# Float_Main_PCB.net
KiCad netlist of a schematic drawn in Altium Designer
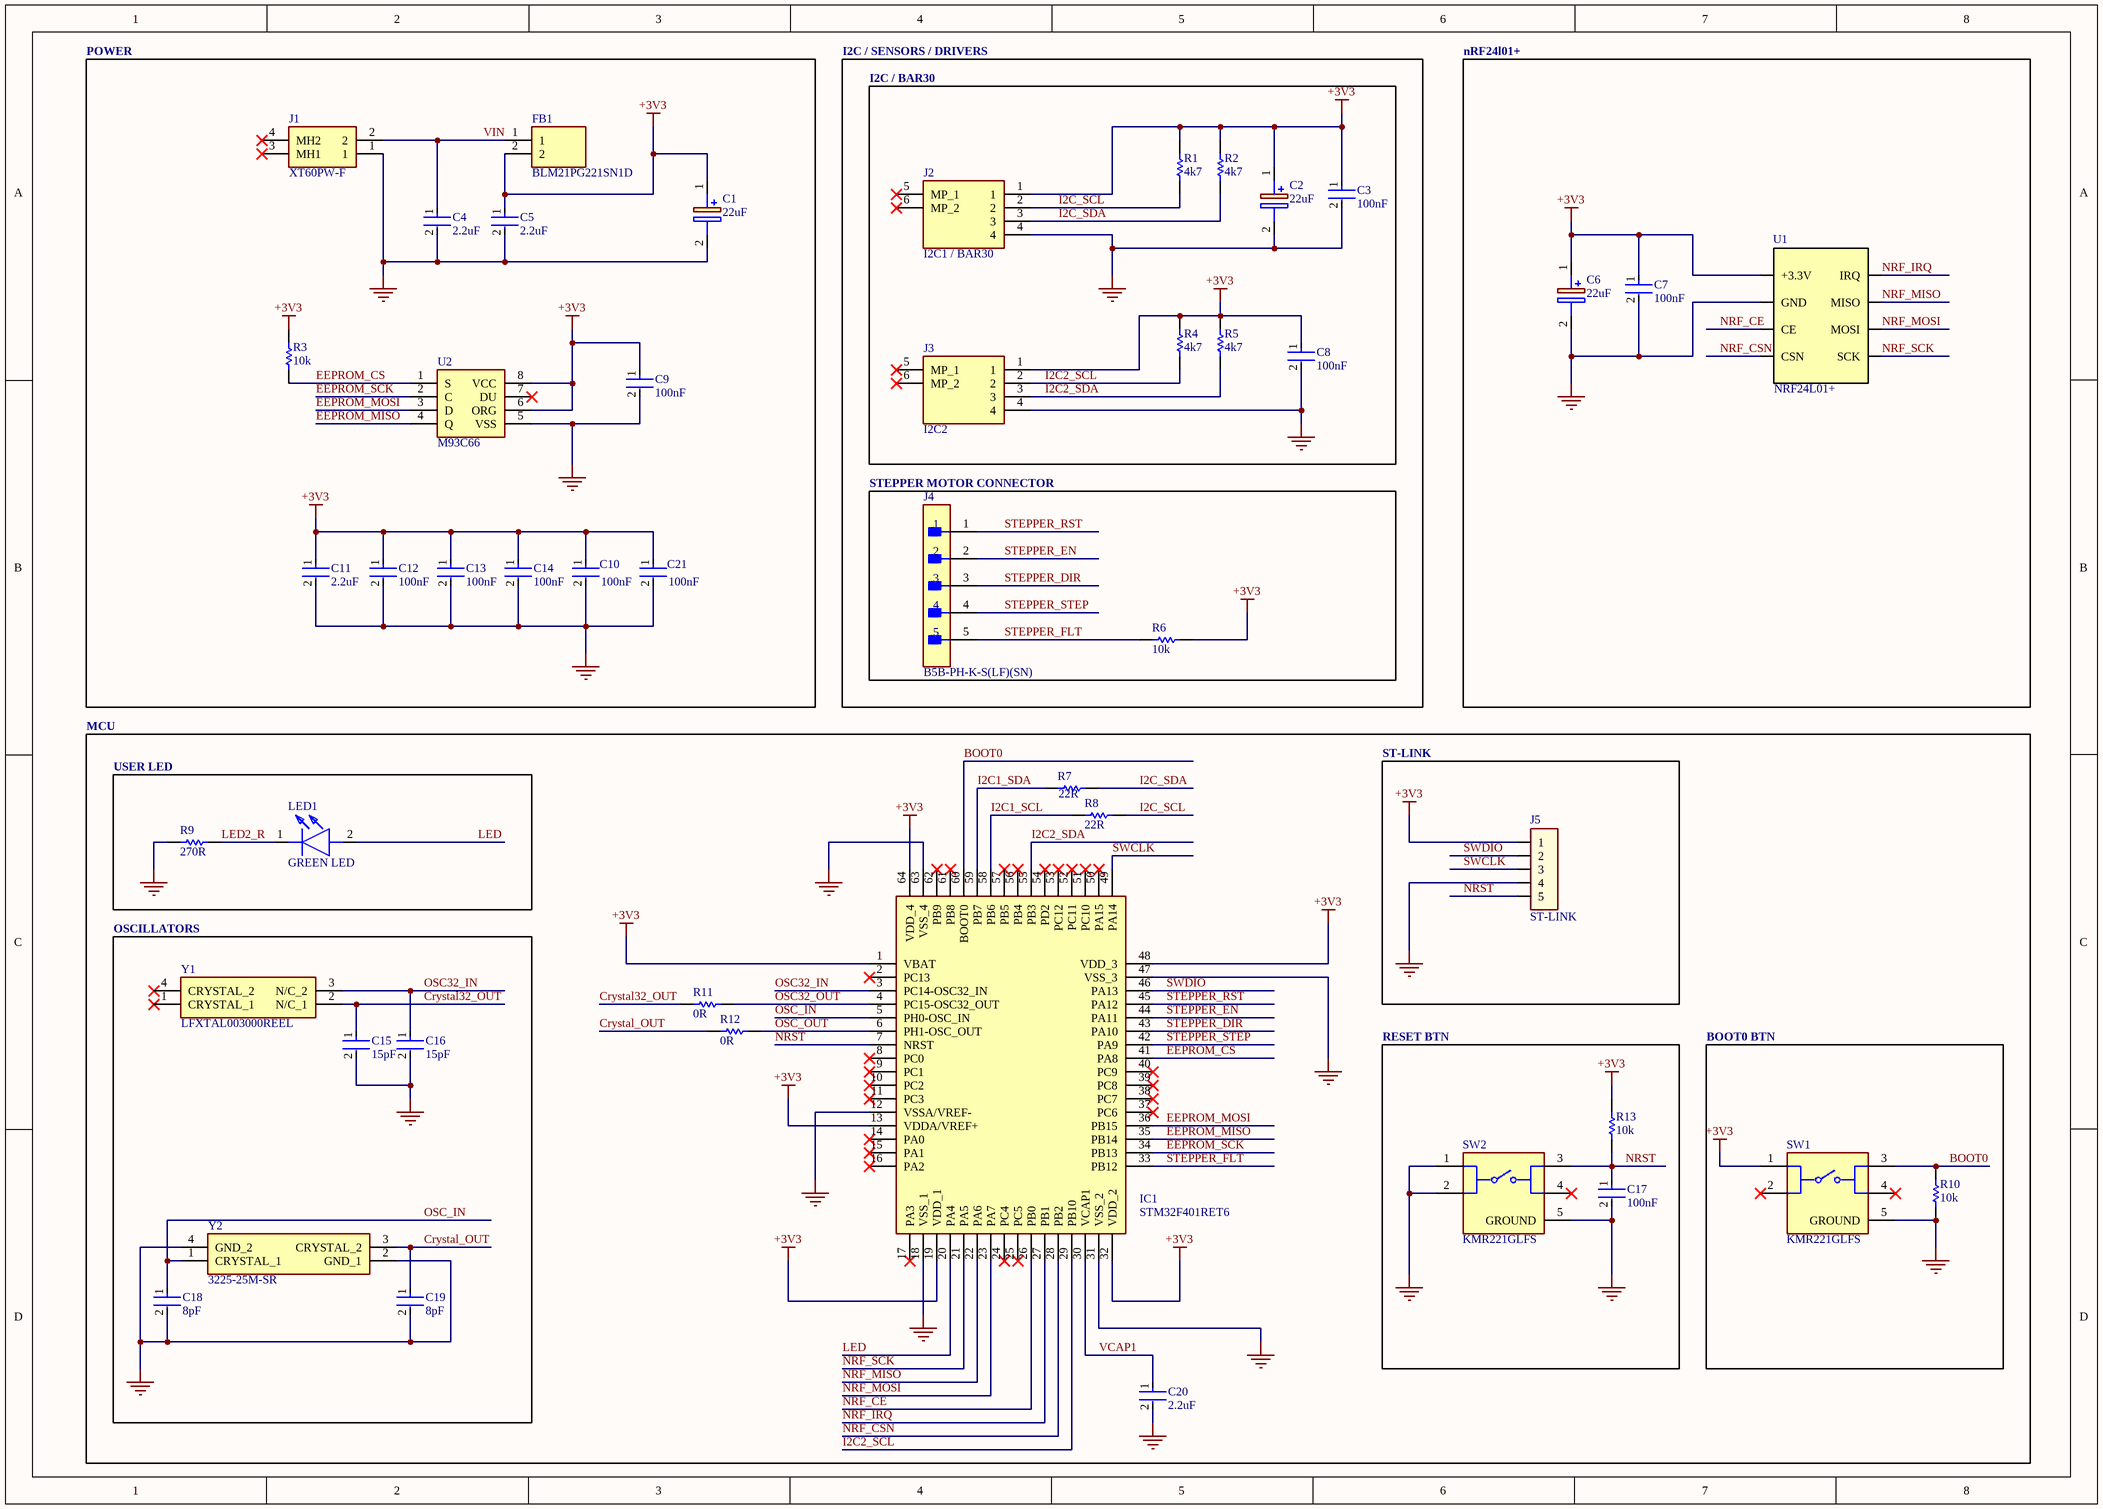
[diagram p0: Float_Main_PCB.SchDoc]

(export (version "E")
  (design (tool "Eeschema 10.0.6"))
  (components
    (comp (ref "C1")
      (value "22uF")
      (footprint "SamacSys:EEE1AA220WR")
      (description "Capacitor Polarised")
      (fields (field (name "MANUFACTURER_PART_NUMBER") "EEE1CA100SR"))
      (libsource (lib "*") (part "EEE1CA100SR"))
    )
    (comp (ref "C2")
      (value "22uF")
      (footprint "SamacSys:EEE1AA220WR")
      (description "Capacitor Polarised")
      (fields (field (name "MANUFACTURER_PART_NUMBER") "EEE1CA100SR"))
      (libsource (lib "*") (part "EEE1CA100SR"))
    )
    (comp (ref "C3")
      (value "100nF")
      (footprint "FP-0805-L_2_01_0_2-W_1_25-MFG")
      (fields (field (name "TOLERANCE") "10%") (field (name "VOLTAGE") "10V"))
      (libsource (lib "Altium Content Vault") (part "b4654b650e69147ec39a6b967a45e02"))
    )
    (comp (ref "C4")
      (value "2.2uF")
      (footprint "FP-0805-L_2_01_0_2-W_1_25-MFG")
      (fields (field (name "TOLERANCE") "10%") (field (name "VOLTAGE") "10V"))
      (libsource (lib "Altium Content Vault") (part "b4654b650e69147ec39a6b967a45e02"))
    )
    (comp (ref "C5")
      (value "2.2uF")
      (footprint "FP-0805-L_2_01_0_2-W_1_25-MFG")
      (fields (field (name "TOLERANCE") "10%") (field (name "VOLTAGE") "10V"))
      (libsource (lib "Altium Content Vault") (part "b4654b650e69147ec39a6b967a45e02"))
    )
    (comp (ref "C6")
      (value "22uF")
      (footprint "SamacSys:EEE1AA220WR")
      (description "Capacitor Polarised")
      (fields (field (name "MANUFACTURER_PART_NUMBER") "EEE1CA100SR"))
      (libsource (lib "*") (part "EEE1CA100SR"))
    )
    (comp (ref "C7")
      (value "100nF")
      (footprint "FP-0805-L_2_01_0_2-W_1_25-MFG")
      (fields (field (name "TOLERANCE") "10%") (field (name "VOLTAGE") "10V"))
      (libsource (lib "Altium Content Vault") (part "b4654b650e69147ec39a6b967a45e02"))
    )
    (comp (ref "C8")
      (value "100nF")
      (footprint "FP-0805-L_2_01_0_2-W_1_25-MFG")
      (fields (field (name "TOLERANCE") "10%") (field (name "VOLTAGE") "10V"))
      (libsource (lib "Altium Content Vault") (part "b4654b650e69147ec39a6b967a45e02"))
    )
    (comp (ref "C9")
      (value "100nF")
      (footprint "FP-0805-L_2_01_0_2-W_1_25-MFG")
      (fields (field (name "TOLERANCE") "10%") (field (name "VOLTAGE") "10V"))
      (libsource (lib "Altium Content Vault") (part "b4654b650e69147ec39a6b967a45e02"))
    )
    (comp (ref "C10")
      (value "100nF")
      (footprint "FP-0805-L_2_01_0_2-W_1_25-MFG")
      (fields (field (name "TOLERANCE") "10%") (field (name "VOLTAGE") "10V"))
      (libsource (lib "Altium Content Vault") (part "b4654b650e69147ec39a6b967a45e02"))
    )
    (comp (ref "C11")
      (value "2.2uF")
      (footprint "FP-0805-L_2_01_0_2-W_1_25-MFG")
      (fields (field (name "TOLERANCE") "10%") (field (name "VOLTAGE") "10V"))
      (libsource (lib "Altium Content Vault") (part "b4654b650e69147ec39a6b967a45e02"))
    )
    (comp (ref "C12")
      (value "100nF")
      (footprint "FP-0805-L_2_01_0_2-W_1_25-MFG")
      (fields (field (name "TOLERANCE") "10%") (field (name "VOLTAGE") "10V"))
      (libsource (lib "Altium Content Vault") (part "b4654b650e69147ec39a6b967a45e02"))
    )
    (comp (ref "C13")
      (value "100nF")
      (footprint "FP-0805-L_2_01_0_2-W_1_25-MFG")
      (fields (field (name "TOLERANCE") "10%") (field (name "VOLTAGE") "10V"))
      (libsource (lib "Altium Content Vault") (part "b4654b650e69147ec39a6b967a45e02"))
    )
    (comp (ref "C14")
      (value "100nF")
      (footprint "FP-0805-L_2_01_0_2-W_1_25-MFG")
      (fields (field (name "TOLERANCE") "10%") (field (name "VOLTAGE") "10V"))
      (libsource (lib "Altium Content Vault") (part "b4654b650e69147ec39a6b967a45e02"))
    )
    (comp (ref "C15")
      (value "15pF")
      (footprint "FP-0805-L_2_01_0_2-W_1_25-MFG")
      (fields (field (name "TOLERANCE") "10%") (field (name "VOLTAGE") "10V"))
      (libsource (lib "Altium Content Vault") (part "b4654b650e69147ec39a6b967a45e02"))
    )
    (comp (ref "C16")
      (value "15pF")
      (footprint "FP-0805-L_2_01_0_2-W_1_25-MFG")
      (fields (field (name "TOLERANCE") "10%") (field (name "VOLTAGE") "10V"))
      (libsource (lib "Altium Content Vault") (part "b4654b650e69147ec39a6b967a45e02"))
    )
    (comp (ref "C17")
      (value "100nF")
      (footprint "FP-0805-L_2_01_0_2-W_1_25-MFG")
      (fields (field (name "TOLERANCE") "10%") (field (name "VOLTAGE") "10V"))
      (libsource (lib "Altium Content Vault") (part "b4654b650e69147ec39a6b967a45e02"))
    )
    (comp (ref "C18")
      (value "8pF")
      (footprint "FP-0805-L_2_01_0_2-W_1_25-MFG")
      (fields (field (name "TOLERANCE") "10%") (field (name "VOLTAGE") "10V"))
      (libsource (lib "Altium Content Vault") (part "b4654b650e69147ec39a6b967a45e02"))
    )
    (comp (ref "C19")
      (value "8pF")
      (footprint "FP-0805-L_2_01_0_2-W_1_25-MFG")
      (fields (field (name "TOLERANCE") "10%") (field (name "VOLTAGE") "10V"))
      (libsource (lib "Altium Content Vault") (part "b4654b650e69147ec39a6b967a45e02"))
    )
    (comp (ref "C20")
      (value "2.2uF")
      (footprint "FP-0805-L_2_01_0_2-W_1_25-MFG")
      (fields (field (name "TOLERANCE") "10%") (field (name "VOLTAGE") "10V"))
      (libsource (lib "Altium Content Vault") (part "b4654b650e69147ec39a6b967a45e02"))
    )
    (comp (ref "C21")
      (value "100nF")
      (footprint "FP-0805-L_2_01_0_2-W_1_25-MFG")
      (fields (field (name "TOLERANCE") "10%") (field (name "VOLTAGE") "10V"))
      (libsource (lib "Altium Content Vault") (part "b4654b650e69147ec39a6b967a45e02"))
    )
    (comp (ref "FB1")
      (value "BLM21PG221SN1D")
      (footprint "SamacSys:BEADC2012X105N")
      (description "Ferrite Bead")
      (fields (field (name "MOUSER PART NUMBER") "81-BLM21P221SG"))
      (libsource (lib "*") (part "BLM21PG221SN1D"))
    )
    (comp (ref "IC1")
      (value "STM32F401RET6")
      (footprint "SamacSys:QFP50P1200X1200X160-64N")
      (description "Integrated Circuit")
      (fields (field (name "MOUSER PART NUMBER") "511-STM32F401RET6"))
      (libsource (lib "*") (part "STM32F401RET6"))
    )
    (comp (ref "J1")
      (value "XT60PW-F")
      (footprint "SamacSys:XT60PWF")
      (description "Connector")
      (libsource (lib "*") (part "XT60PW-F"))
    )
    (comp (ref "J2")
      (value "I2C1 / BAR30")
      (footprint "SamacSys:SM04BGHSTBLFSN")
      (description "Connector")
      (fields (field (name "MANUFACTURER_PART_NUMBER") "SM04B-GHS-TB (LF)(SN)"))
      (libsource (lib "*") (part "SM04B-GHS-TB__LF__SN_"))
    )
    (comp (ref "J3")
      (value "I2C2")
      (footprint "SamacSys:SM04BGHSTBLFSN")
      (description "Connector")
      (fields (field (name "MANUFACTURER_PART_NUMBER") "SM04B-GHS-TB (LF)(SN)"))
      (libsource (lib "*") (part "SM04B-GHS-TB__LF__SN_"))
    )
    (comp (ref "J4")
      (value "B5B-PH-K-S(LF)(SN)")
      (footprint "FP-B5B-PH-K-S_LF_SN-MFG")
      (description "CONN HEADER VERT 5POS 2MM")
      (libsource (lib "Altium Content Vault") (part "bf93c07fd2649a848d0ec8585582aab"))
    )
    (comp (ref "J5")
      (value "ST-LINK")
      (footprint "goldpin5")
      (libsource (lib "Akademia Górniczo Hutnicza W Krakowie") (part "goldpin_5"))
    )
    (comp (ref "LED1")
      (value "GREEN LED")
      (footprint "SamacSys:LEDC2012X80N")
      (description "LED")
      (fields
        (field (name "MANUFACTURER_PART_NUMBER") "HSMG-C170")
        (field (name "MOUSER PART NUMBER") "630-HSMG-C170")
      )
      (libsource (lib "*") (part "HSMG-C170"))
    )
    (comp (ref "R1")
      (value "4k7")
      (footprint "RESC2013X60X35ML10T20")
      (fields (field (name "TOLERANCE") "1%") (field (name "MANUFACTURER") "Yageo"))
      (libsource (lib "Altium Content Vault") (part "RES-2"))
    )
    (comp (ref "R2")
      (value "4k7")
      (footprint "RESC2013X60X35ML10T20")
      (fields (field (name "TOLERANCE") "1%") (field (name "MANUFACTURER") "Yageo"))
      (libsource (lib "Altium Content Vault") (part "RES-2"))
    )
    (comp (ref "R3")
      (value "10k")
      (footprint "RESC2013X60X35ML10T20")
      (fields (field (name "TOLERANCE") "1%") (field (name "MANUFACTURER") "Yageo"))
      (libsource (lib "Altium Content Vault") (part "RES-2"))
    )
    (comp (ref "R4")
      (value "4k7")
      (footprint "RESC2013X60X35ML10T20")
      (fields (field (name "TOLERANCE") "1%") (field (name "MANUFACTURER") "Yageo"))
      (libsource (lib "Altium Content Vault") (part "RES-2"))
    )
    (comp (ref "R5")
      (value "4k7")
      (footprint "RESC2013X60X35ML10T20")
      (fields (field (name "TOLERANCE") "1%") (field (name "MANUFACTURER") "Yageo"))
      (libsource (lib "Altium Content Vault") (part "RES-2"))
    )
    (comp (ref "R6")
      (value "10k")
      (footprint "RESC2013X60X35ML10T20")
      (fields (field (name "TOLERANCE") "1%") (field (name "MANUFACTURER") "Yageo"))
      (libsource (lib "Altium Content Vault") (part "RES-2"))
    )
    (comp (ref "R7")
      (value "22R")
      (footprint "RESC2013X60X35ML10T20")
      (fields (field (name "TOLERANCE") "1%") (field (name "MANUFACTURER") "Yageo"))
      (libsource (lib "Altium Content Vault") (part "RES-2"))
    )
    (comp (ref "R8")
      (value "22R")
      (footprint "RESC2013X60X35ML10T20")
      (fields (field (name "TOLERANCE") "1%") (field (name "MANUFACTURER") "Yageo"))
      (libsource (lib "Altium Content Vault") (part "RES-2"))
    )
    (comp (ref "R9")
      (value "270R")
      (footprint "RESC2013X60X35ML10T20")
      (fields (field (name "TOLERANCE") "1%") (field (name "MANUFACTURER") "Yageo"))
      (libsource (lib "Altium Content Vault") (part "RES-2"))
    )
    (comp (ref "R10")
      (value "10k")
      (footprint "RESC2013X60X35ML10T20")
      (fields (field (name "TOLERANCE") "1%") (field (name "MANUFACTURER") "Yageo"))
      (libsource (lib "Altium Content Vault") (part "RES-2"))
    )
    (comp (ref "R11")
      (value "0R")
      (footprint "RESC2013X60X35ML10T20")
      (fields (field (name "TOLERANCE") "1%") (field (name "MANUFACTURER") "Yageo"))
      (libsource (lib "Altium Content Vault") (part "RES-2"))
    )
    (comp (ref "R12")
      (value "0R")
      (footprint "RESC2013X60X35ML10T20")
      (fields (field (name "TOLERANCE") "1%") (field (name "MANUFACTURER") "Yageo"))
      (libsource (lib "Altium Content Vault") (part "RES-2"))
    )
    (comp (ref "R13")
      (value "10k")
      (footprint "RESC2013X60X35ML10T20")
      (fields (field (name "TOLERANCE") "1%") (field (name "MANUFACTURER") "Yageo"))
      (libsource (lib "Altium Content Vault") (part "RES-2"))
    )
    (comp (ref "SW1")
      (value "KMR221GLFS")
      (footprint "FP-KMR221GLFS-MFG")
      (description "SWITCH TACTILE SPST-NO 0.05A 32V")
      (libsource (lib "Altium Content Vault") (part "067e1cfe0b8977aedbfee7786663f4c"))
    )
    (comp (ref "SW2")
      (value "KMR221GLFS")
      (footprint "FP-KMR221GLFS-MFG")
      (description "SWITCH TACTILE SPST-NO 0.05A 32V")
      (libsource (lib "Altium Content Vault") (part "067e1cfe0b8977aedbfee7786663f4c"))
    )
    (comp (ref "U1")
      (value "NRF24L01+ SMD")
      (footprint "PCBComponent_1")
      (libsource (lib "NRF24L01+SMD") (part "NRF24L01+ SMD"))
    )
    (comp (ref "U2")
      (value "M93C66")
      (footprint "SamacSys:SOIC127P600X175-8N")
      (description "Integrated Circuit")
      (fields
        (field (name "MANUFACTURER_PART_NUMBER") "M93C66-WMN6TP")
        (field (name "MOUSER PART NUMBER") "511-M93C66-WMN6TP")
      )
      (libsource (lib "*") (part "M93C66-WMN6TP"))
    )
    (comp (ref "Y1")
      (value "LFXTAL003000REEL")
      (footprint "SamacSys:LFXTAL003000REEL")
      (description "Crystal or Oscillator")
      (fields (field (name "MOUSER PART NUMBER") "449-LFXTAL003000REEL"))
      (libsource (lib "*") (part "LFXTAL003000REEL"))
    )
    (comp (ref "Y2")
      (value "3225-25M-SR")
      (footprint "SamacSys:322525MSR")
      (description "Crystal or Oscillator")
      (libsource (lib "SamacSys") (part "3225-25M-SR"))
    )
  )
  (nets
    (net (code "1") (name "+3V3") (class "Default")
      (node (ref "C1") (pin "1") (pinfunction "+_1") (pintype "passive"))
      (node (ref "C10") (pin "1") (pinfunction "1_1") (pintype "passive"))
      (node (ref "C11") (pin "1") (pinfunction "1_1") (pintype "passive"))
      (node (ref "C12") (pin "1") (pinfunction "1_1") (pintype "passive"))
      (node (ref "C13") (pin "1") (pinfunction "1_1") (pintype "passive"))
      (node (ref "C14") (pin "1") (pinfunction "1_1") (pintype "passive"))
      (node (ref "C2") (pin "1") (pinfunction "+_1") (pintype "passive"))
      (node (ref "C21") (pin "1") (pinfunction "1_1") (pintype "passive"))
      (node (ref "C3") (pin "1") (pinfunction "1_1") (pintype "passive"))
      (node (ref "C5") (pin "1") (pinfunction "1_1") (pintype "passive"))
      (node (ref "C6") (pin "1") (pinfunction "+_1") (pintype "passive"))
      (node (ref "C7") (pin "1") (pinfunction "1_1") (pintype "passive"))
      (node (ref "C8") (pin "1") (pinfunction "1_1") (pintype "passive"))
      (node (ref "C9") (pin "1") (pinfunction "1_1") (pintype "passive"))
      (node (ref "FB1") (pin "2") (pinfunction "2_2") (pintype "passive"))
      (node (ref "IC1") (pin "1") (pinfunction "VBAT_1") (pintype "passive"))
      (node (ref "IC1") (pin "13") (pinfunction "VDDA/VREF+_13") (pintype "passive"))
      (node (ref "IC1") (pin "19") (pinfunction "VDD_1_19") (pintype "passive"))
      (node (ref "IC1") (pin "32") (pinfunction "VDD_2_32") (pintype "passive"))
      (node (ref "IC1") (pin "48") (pinfunction "VDD_3_48") (pintype "passive"))
      (node (ref "IC1") (pin "64") (pinfunction "VDD_4_64") (pintype "passive"))
      (node (ref "J2") (pin "1") (pinfunction "1_1") (pintype "passive"))
      (node (ref "J3") (pin "1") (pinfunction "1_1") (pintype "passive"))
      (node (ref "J5") (pin "1") (pinfunction "1_1") (pintype "passive"))
      (node (ref "R1") (pin "2") (pinfunction "2_2") (pintype "passive"))
      (node (ref "R13") (pin "2") (pinfunction "2_2") (pintype "passive"))
      (node (ref "R2") (pin "1") (pinfunction "1_1") (pintype "passive"))
      (node (ref "R3") (pin "1") (pinfunction "1_1") (pintype "passive"))
      (node (ref "R4") (pin "2") (pinfunction "2_2") (pintype "passive"))
      (node (ref "R5") (pin "1") (pinfunction "1_1") (pintype "passive"))
      (node (ref "R6") (pin "1") (pinfunction "1_1") (pintype "passive"))
      (node (ref "SW1") (pin "1") (pinfunction "1_1") (pintype "passive"))
      (node (ref "U1") (pin "1") (pinfunction "+3.3V_1") (pintype "passive"))
      (node (ref "U2") (pin "6") (pinfunction "ORG_6") (pintype "passive"))
      (node (ref "U2") (pin "8") (pinfunction "VCC_8") (pintype "passive"))
    )
    (net (code "2") (name "/BOOT0") (class "Default")
      (node (ref "IC1") (pin "60") (pinfunction "BOOT0_60") (pintype "passive"))
      (node (ref "R10") (pin "1") (pinfunction "1_1") (pintype "passive"))
      (node (ref "SW1") (pin "3") (pinfunction "3_3") (pintype "passive"))
    )
    (net (code "3") (name "/Crystal32_OUT") (class "Default")
      (node (ref "C15") (pin "1") (pinfunction "1_1") (pintype "passive"))
      (node (ref "R11") (pin "1") (pinfunction "1_1") (pintype "passive"))
      (node (ref "Y1") (pin "2") (pinfunction "N/C_1_2") (pintype "passive"))
    )
    (net (code "4") (name "/Crystal_OUT") (class "Default")
      (node (ref "C19") (pin "1") (pinfunction "1_1") (pintype "passive"))
      (node (ref "R12") (pin "2") (pinfunction "2_2") (pintype "passive"))
      (node (ref "Y2") (pin "3") (pinfunction "CRYSTAL_2_3") (pintype "passive"))
    )
    (net (code "5") (name "/EEPROM_CS") (class "Default")
      (node (ref "IC1") (pin "41") (pinfunction "PA8_41") (pintype "passive"))
      (node (ref "R3") (pin "2") (pinfunction "2_2") (pintype "passive"))
      (node (ref "U2") (pin "1") (pinfunction "S_1") (pintype "passive"))
    )
    (net (code "6") (name "/EEPROM_MISO") (class "Default")
      (node (ref "IC1") (pin "35") (pinfunction "PB14_35") (pintype "passive"))
      (node (ref "U2") (pin "4") (pinfunction "Q_4") (pintype "passive"))
    )
    (net (code "7") (name "/EEPROM_MOSI") (class "Default")
      (node (ref "IC1") (pin "36") (pinfunction "PB15_36") (pintype "passive"))
      (node (ref "U2") (pin "3") (pinfunction "D_3") (pintype "passive"))
    )
    (net (code "8") (name "/EEPROM_SCK") (class "Default")
      (node (ref "IC1") (pin "34") (pinfunction "PB13_34") (pintype "passive"))
      (node (ref "U2") (pin "2") (pinfunction "C_2") (pintype "passive"))
    )
    (net (code "9") (name "/I2C1_SCL") (class "Default")
      (node (ref "IC1") (pin "58") (pinfunction "PB6_58") (pintype "passive"))
      (node (ref "R8") (pin "2") (pinfunction "2_2") (pintype "passive"))
    )
    (net (code "10") (name "/I2C1_SDA") (class "Default")
      (node (ref "IC1") (pin "59") (pinfunction "PB7_59") (pintype "passive"))
      (node (ref "R7") (pin "2") (pinfunction "2_2") (pintype "passive"))
    )
    (net (code "11") (name "/I2C2_SCL") (class "Default")
      (node (ref "IC1") (pin "29") (pinfunction "PB10_29") (pintype "passive"))
      (node (ref "J3") (pin "2") (pinfunction "2_2") (pintype "passive"))
      (node (ref "R4") (pin "1") (pinfunction "1_1") (pintype "passive"))
    )
    (net (code "12") (name "/I2C2_SDA") (class "Default")
      (node (ref "IC1") (pin "55") (pinfunction "PB3_55") (pintype "passive"))
      (node (ref "J3") (pin "3") (pinfunction "3_3") (pintype "passive"))
      (node (ref "R5") (pin "2") (pinfunction "2_2") (pintype "passive"))
    )
    (net (code "13") (name "/I2C_SCL") (class "Default")
      (node (ref "J2") (pin "2") (pinfunction "2_2") (pintype "passive"))
      (node (ref "R1") (pin "1") (pinfunction "1_1") (pintype "passive"))
      (node (ref "R8") (pin "1") (pinfunction "1_1") (pintype "passive"))
    )
    (net (code "14") (name "/I2C_SDA") (class "Default")
      (node (ref "J2") (pin "3") (pinfunction "3_3") (pintype "passive"))
      (node (ref "R2") (pin "2") (pinfunction "2_2") (pintype "passive"))
      (node (ref "R7") (pin "1") (pinfunction "1_1") (pintype "passive"))
    )
    (net (code "15") (name "/LED") (class "Default")
      (node (ref "IC1") (pin "20") (pinfunction "PA4_20") (pintype "passive"))
      (node (ref "LED1") (pin "2") (pinfunction "A_2") (pintype "passive"))
    )
    (net (code "16") (name "/LED2_R") (class "Default")
      (node (ref "LED1") (pin "1") (pinfunction "K_1") (pintype "passive"))
      (node (ref "R9") (pin "2") (pinfunction "2_2") (pintype "passive"))
    )
    (net (code "17") (name "/NRF_CE") (class "Default")
      (node (ref "IC1") (pin "26") (pinfunction "PB0_26") (pintype "passive"))
      (node (ref "U1") (pin "3") (pinfunction "CE_3") (pintype "passive"))
    )
    (net (code "18") (name "/NRF_CSN") (class "Default")
      (node (ref "IC1") (pin "28") (pinfunction "PB2_28") (pintype "passive"))
      (node (ref "U1") (pin "4") (pinfunction "CSN_4") (pintype "passive"))
    )
    (net (code "19") (name "/NRF_IRQ") (class "Default")
      (node (ref "IC1") (pin "27") (pinfunction "PB1_27") (pintype "passive"))
      (node (ref "U1") (pin "8") (pinfunction "IRQ_8") (pintype "passive"))
    )
    (net (code "20") (name "/NRF_MISO") (class "Default")
      (node (ref "IC1") (pin "22") (pinfunction "PA6_22") (pintype "passive"))
      (node (ref "U1") (pin "7") (pinfunction "MISO_7") (pintype "passive"))
    )
    (net (code "21") (name "/NRF_MOSI") (class "Default")
      (node (ref "IC1") (pin "23") (pinfunction "PA7_23") (pintype "passive"))
      (node (ref "U1") (pin "6") (pinfunction "MOSI_6") (pintype "passive"))
    )
    (net (code "22") (name "/NRF_SCK") (class "Default")
      (node (ref "IC1") (pin "21") (pinfunction "PA5_21") (pintype "passive"))
      (node (ref "U1") (pin "5") (pinfunction "SCK_5") (pintype "passive"))
    )
    (net (code "23") (name "/NRST") (class "Default")
      (node (ref "C17") (pin "1") (pinfunction "1_1") (pintype "passive"))
      (node (ref "IC1") (pin "7") (pinfunction "NRST_7") (pintype "passive"))
      (node (ref "J5") (pin "5") (pinfunction "5_5") (pintype "passive"))
      (node (ref "R13") (pin "1") (pinfunction "1_1") (pintype "passive"))
      (node (ref "SW2") (pin "3") (pinfunction "3_3") (pintype "passive"))
    )
    (net (code "24") (name "/OSC32_IN") (class "Default")
      (node (ref "C16") (pin "1") (pinfunction "1_1") (pintype "passive"))
      (node (ref "IC1") (pin "3") (pinfunction "PC14-OSC32_IN_3") (pintype "passive"))
      (node (ref "Y1") (pin "3") (pinfunction "N/C_2_3") (pintype "passive"))
    )
    (net (code "25") (name "/OSC32_OUT") (class "Default")
      (node (ref "IC1") (pin "4") (pinfunction "PC15-OSC32_OUT_4") (pintype "passive"))
      (node (ref "R11") (pin "2") (pinfunction "2_2") (pintype "passive"))
    )
    (net (code "26") (name "/OSC_IN") (class "Default")
      (node (ref "C18") (pin "1") (pinfunction "1_1") (pintype "passive"))
      (node (ref "IC1") (pin "5") (pinfunction "PH0-OSC_IN_5") (pintype "passive"))
      (node (ref "Y2") (pin "1") (pinfunction "CRYSTAL_1_1") (pintype "passive"))
    )
    (net (code "27") (name "/OSC_OUT") (class "Default")
      (node (ref "IC1") (pin "6") (pinfunction "PH1-OSC_OUT_6") (pintype "passive"))
      (node (ref "R12") (pin "1") (pinfunction "1_1") (pintype "passive"))
    )
    (net (code "28") (name "/STEPPER_DIR") (class "Default")
      (node (ref "IC1") (pin "43") (pinfunction "PA10_43") (pintype "passive"))
      (node (ref "J4") (pin "3") (pinfunction "3_3") (pintype "passive"))
    )
    (net (code "29") (name "/STEPPER_EN") (class "Default")
      (node (ref "IC1") (pin "44") (pinfunction "PA11_44") (pintype "passive"))
      (node (ref "J4") (pin "2") (pinfunction "2_2") (pintype "passive"))
    )
    (net (code "30") (name "/STEPPER_FLT") (class "Default")
      (node (ref "IC1") (pin "33") (pinfunction "PB12_33") (pintype "passive"))
      (node (ref "J4") (pin "5") (pinfunction "5_5") (pintype "passive"))
      (node (ref "R6") (pin "2") (pinfunction "2_2") (pintype "passive"))
    )
    (net (code "31") (name "/STEPPER_RST") (class "Default")
      (node (ref "IC1") (pin "45") (pinfunction "PA12_45") (pintype "passive"))
      (node (ref "J4") (pin "1") (pinfunction "1_1") (pintype "passive"))
    )
    (net (code "32") (name "/STEPPER_STEP") (class "Default")
      (node (ref "IC1") (pin "42") (pinfunction "PA9_42") (pintype "passive"))
      (node (ref "J4") (pin "4") (pinfunction "4_4") (pintype "passive"))
    )
    (net (code "33") (name "/SWCLK") (class "Default")
      (node (ref "IC1") (pin "49") (pinfunction "PA14_49") (pintype "passive"))
      (node (ref "J5") (pin "3") (pinfunction "3_3") (pintype "passive"))
    )
    (net (code "34") (name "/SWDIO") (class "Default")
      (node (ref "IC1") (pin "46") (pinfunction "PA13_46") (pintype "passive"))
      (node (ref "J5") (pin "2") (pinfunction "2_2") (pintype "passive"))
    )
    (net (code "35") (name "/VCAP1") (class "Default")
      (node (ref "C20") (pin "1") (pinfunction "1_1") (pintype "passive"))
      (node (ref "IC1") (pin "30") (pinfunction "VCAP1_30") (pintype "passive"))
    )
    (net (code "36") (name "/VIN") (class "Default")
      (node (ref "C4") (pin "1") (pinfunction "1_1") (pintype "passive"))
      (node (ref "FB1") (pin "1") (pinfunction "1_1") (pintype "passive"))
      (node (ref "J1") (pin "2") (pinfunction "2_2") (pintype "passive"))
    )
    (net (code "37") (name "GND") (class "Default")
      (node (ref "C1") (pin "2") (pinfunction "-_2") (pintype "passive"))
      (node (ref "C10") (pin "2") (pinfunction "2_2") (pintype "passive"))
      (node (ref "C11") (pin "2") (pinfunction "2_2") (pintype "passive"))
      (node (ref "C12") (pin "2") (pinfunction "2_2") (pintype "passive"))
      (node (ref "C13") (pin "2") (pinfunction "2_2") (pintype "passive"))
      (node (ref "C14") (pin "2") (pinfunction "2_2") (pintype "passive"))
      (node (ref "C15") (pin "2") (pinfunction "2_2") (pintype "passive"))
      (node (ref "C16") (pin "2") (pinfunction "2_2") (pintype "passive"))
      (node (ref "C17") (pin "2") (pinfunction "2_2") (pintype "passive"))
      (node (ref "C18") (pin "2") (pinfunction "2_2") (pintype "passive"))
      (node (ref "C19") (pin "2") (pinfunction "2_2") (pintype "passive"))
      (node (ref "C2") (pin "2") (pinfunction "-_2") (pintype "passive"))
      (node (ref "C20") (pin "2") (pinfunction "2_2") (pintype "passive"))
      (node (ref "C21") (pin "2") (pinfunction "2_2") (pintype "passive"))
      (node (ref "C3") (pin "2") (pinfunction "2_2") (pintype "passive"))
      (node (ref "C4") (pin "2") (pinfunction "2_2") (pintype "passive"))
      (node (ref "C5") (pin "2") (pinfunction "2_2") (pintype "passive"))
      (node (ref "C6") (pin "2") (pinfunction "-_2") (pintype "passive"))
      (node (ref "C7") (pin "2") (pinfunction "2_2") (pintype "passive"))
      (node (ref "C8") (pin "2") (pinfunction "2_2") (pintype "passive"))
      (node (ref "C9") (pin "2") (pinfunction "2_2") (pintype "passive"))
      (node (ref "IC1") (pin "12") (pinfunction "VSSA/VREF-_12") (pintype "passive"))
      (node (ref "IC1") (pin "18") (pinfunction "VSS_1_18") (pintype "passive"))
      (node (ref "IC1") (pin "31") (pinfunction "VSS_2_31") (pintype "passive"))
      (node (ref "IC1") (pin "47") (pinfunction "VSS_3_47") (pintype "passive"))
      (node (ref "IC1") (pin "63") (pinfunction "VSS_4_63") (pintype "passive"))
      (node (ref "J1") (pin "1") (pinfunction "1_1") (pintype "passive"))
      (node (ref "J2") (pin "4") (pinfunction "4_4") (pintype "passive"))
      (node (ref "J3") (pin "4") (pinfunction "4_4") (pintype "passive"))
      (node (ref "J5") (pin "4") (pinfunction "4_4") (pintype "passive"))
      (node (ref "R10") (pin "2") (pinfunction "2_2") (pintype "passive"))
      (node (ref "R9") (pin "1") (pinfunction "1_1") (pintype "passive"))
      (node (ref "SW1") (pin "5") (pinfunction "GROUND_5") (pintype "power_in"))
      (node (ref "SW2") (pin "1") (pinfunction "1_1") (pintype "passive"))
      (node (ref "SW2") (pin "2") (pinfunction "2_2") (pintype "passive"))
      (node (ref "SW2") (pin "5") (pinfunction "GROUND_5") (pintype "power_in"))
      (node (ref "U1") (pin "2") (pinfunction "GND_2") (pintype "passive"))
      (node (ref "U2") (pin "5") (pinfunction "VSS_5") (pintype "passive"))
      (node (ref "Y2") (pin "2") (pinfunction "GND_1_2") (pintype "passive"))
      (node (ref "Y2") (pin "4") (pinfunction "GND_2_4") (pintype "passive"))
    )
    (net (code "38") (name "unconnected-(IC1-PA0-Pad14)") (class "Default")
      (node (ref "IC1") (pin "14") (pinfunction "PA0_14") (pintype "passive+no_connect"))
    )
    (net (code "39") (name "unconnected-(IC1-PA1-Pad15)") (class "Default")
      (node (ref "IC1") (pin "15") (pinfunction "PA1_15") (pintype "passive+no_connect"))
    )
    (net (code "40") (name "unconnected-(IC1-PA2-Pad16)") (class "Default")
      (node (ref "IC1") (pin "16") (pinfunction "PA2_16") (pintype "passive+no_connect"))
    )
    (net (code "41") (name "unconnected-(IC1-PA3-Pad17)") (class "Default")
      (node (ref "IC1") (pin "17") (pinfunction "PA3_17") (pintype "passive+no_connect"))
    )
    (net (code "42") (name "unconnected-(IC1-PA15-Pad50)") (class "Default")
      (node (ref "IC1") (pin "50") (pinfunction "PA15_50") (pintype "passive+no_connect"))
    )
    (net (code "43") (name "unconnected-(IC1-PB4-Pad56)") (class "Default")
      (node (ref "IC1") (pin "56") (pinfunction "PB4_56") (pintype "passive+no_connect"))
    )
    (net (code "44") (name "unconnected-(IC1-PB5-Pad57)") (class "Default")
      (node (ref "IC1") (pin "57") (pinfunction "PB5_57") (pintype "passive+no_connect"))
    )
    (net (code "45") (name "unconnected-(IC1-PB8-Pad61)") (class "Default")
      (node (ref "IC1") (pin "61") (pinfunction "PB8_61") (pintype "passive+no_connect"))
    )
    (net (code "46") (name "unconnected-(IC1-PB9-Pad62)") (class "Default")
      (node (ref "IC1") (pin "62") (pinfunction "PB9_62") (pintype "passive+no_connect"))
    )
    (net (code "47") (name "unconnected-(IC1-PC0-Pad8)") (class "Default")
      (node (ref "IC1") (pin "8") (pinfunction "PC0_8") (pintype "passive+no_connect"))
    )
    (net (code "48") (name "unconnected-(IC1-PC1-Pad9)") (class "Default")
      (node (ref "IC1") (pin "9") (pinfunction "PC1_9") (pintype "passive+no_connect"))
    )
    (net (code "49") (name "unconnected-(IC1-PC2-Pad10)") (class "Default")
      (node (ref "IC1") (pin "10") (pinfunction "PC2_10") (pintype "passive+no_connect"))
    )
    (net (code "50") (name "unconnected-(IC1-PC3-Pad11)") (class "Default")
      (node (ref "IC1") (pin "11") (pinfunction "PC3_11") (pintype "passive+no_connect"))
    )
    (net (code "51") (name "unconnected-(IC1-PC4-Pad24)") (class "Default")
      (node (ref "IC1") (pin "24") (pinfunction "PC4_24") (pintype "passive+no_connect"))
    )
    (net (code "52") (name "unconnected-(IC1-PC5-Pad25)") (class "Default")
      (node (ref "IC1") (pin "25") (pinfunction "PC5_25") (pintype "passive+no_connect"))
    )
    (net (code "53") (name "unconnected-(IC1-PC6-Pad37)") (class "Default")
      (node (ref "IC1") (pin "37") (pinfunction "PC6_37") (pintype "passive+no_connect"))
    )
    (net (code "54") (name "unconnected-(IC1-PC7-Pad38)") (class "Default")
      (node (ref "IC1") (pin "38") (pinfunction "PC7_38") (pintype "passive+no_connect"))
    )
    (net (code "55") (name "unconnected-(IC1-PC8-Pad39)") (class "Default")
      (node (ref "IC1") (pin "39") (pinfunction "PC8_39") (pintype "passive+no_connect"))
    )
    (net (code "56") (name "unconnected-(IC1-PC9-Pad40)") (class "Default")
      (node (ref "IC1") (pin "40") (pinfunction "PC9_40") (pintype "passive+no_connect"))
    )
    (net (code "57") (name "unconnected-(IC1-PC10-Pad51)") (class "Default")
      (node (ref "IC1") (pin "51") (pinfunction "PC10_51") (pintype "passive+no_connect"))
    )
    (net (code "58") (name "unconnected-(IC1-PC11-Pad52)") (class "Default")
      (node (ref "IC1") (pin "52") (pinfunction "PC11_52") (pintype "passive+no_connect"))
    )
    (net (code "59") (name "unconnected-(IC1-PC12-Pad53)") (class "Default")
      (node (ref "IC1") (pin "53") (pinfunction "PC12_53") (pintype "passive+no_connect"))
    )
    (net (code "60") (name "unconnected-(IC1-PC13-Pad2)") (class "Default")
      (node (ref "IC1") (pin "2") (pinfunction "PC13_2") (pintype "passive+no_connect"))
    )
    (net (code "61") (name "unconnected-(IC1-PD2-Pad54)") (class "Default")
      (node (ref "IC1") (pin "54") (pinfunction "PD2_54") (pintype "passive+no_connect"))
    )
    (net (code "62") (name "unconnected-(J1-MH1-Pad3)") (class "Default")
      (node (ref "J1") (pin "3") (pinfunction "MH1_3") (pintype "passive+no_connect"))
    )
    (net (code "63") (name "unconnected-(J1-MH2-Pad4)") (class "Default")
      (node (ref "J1") (pin "4") (pinfunction "MH2_4") (pintype "passive+no_connect"))
    )
    (net (code "64") (name "unconnected-(J2-MP_1-Pad5)") (class "Default")
      (node (ref "J2") (pin "5") (pinfunction "MP_1_5") (pintype "passive+no_connect"))
    )
    (net (code "65") (name "unconnected-(J2-MP_2-Pad6)") (class "Default")
      (node (ref "J2") (pin "6") (pinfunction "MP_2_6") (pintype "passive+no_connect"))
    )
    (net (code "66") (name "unconnected-(J3-MP_1-Pad5)") (class "Default")
      (node (ref "J3") (pin "5") (pinfunction "MP_1_5") (pintype "passive+no_connect"))
    )
    (net (code "67") (name "unconnected-(J3-MP_2-Pad6)") (class "Default")
      (node (ref "J3") (pin "6") (pinfunction "MP_2_6") (pintype "passive+no_connect"))
    )
    (net (code "68") (name "unconnected-(SW1-Pad2)") (class "Default")
      (node (ref "SW1") (pin "2") (pinfunction "2_2") (pintype "passive+no_connect"))
    )
    (net (code "69") (name "unconnected-(SW1-Pad4)") (class "Default")
      (node (ref "SW1") (pin "4") (pinfunction "4_4") (pintype "passive+no_connect"))
    )
    (net (code "70") (name "unconnected-(SW2-Pad4)") (class "Default")
      (node (ref "SW2") (pin "4") (pinfunction "4_4") (pintype "passive+no_connect"))
    )
    (net (code "71") (name "unconnected-(U2-DU-Pad7)") (class "Default")
      (node (ref "U2") (pin "7") (pinfunction "DU_7") (pintype "passive+no_connect"))
    )
    (net (code "72") (name "unconnected-(Y1-CRYSTAL_1-Pad1)") (class "Default")
      (node (ref "Y1") (pin "1") (pinfunction "CRYSTAL_1_1") (pintype "passive+no_connect"))
    )
    (net (code "73") (name "unconnected-(Y1-CRYSTAL_2-Pad4)") (class "Default")
      (node (ref "Y1") (pin "4") (pinfunction "CRYSTAL_2_4") (pintype "passive+no_connect"))
    )
  )
)
